# ESP32-S_V2.net
KiCad netlist of a schematic drawn in EasyEDA Pro
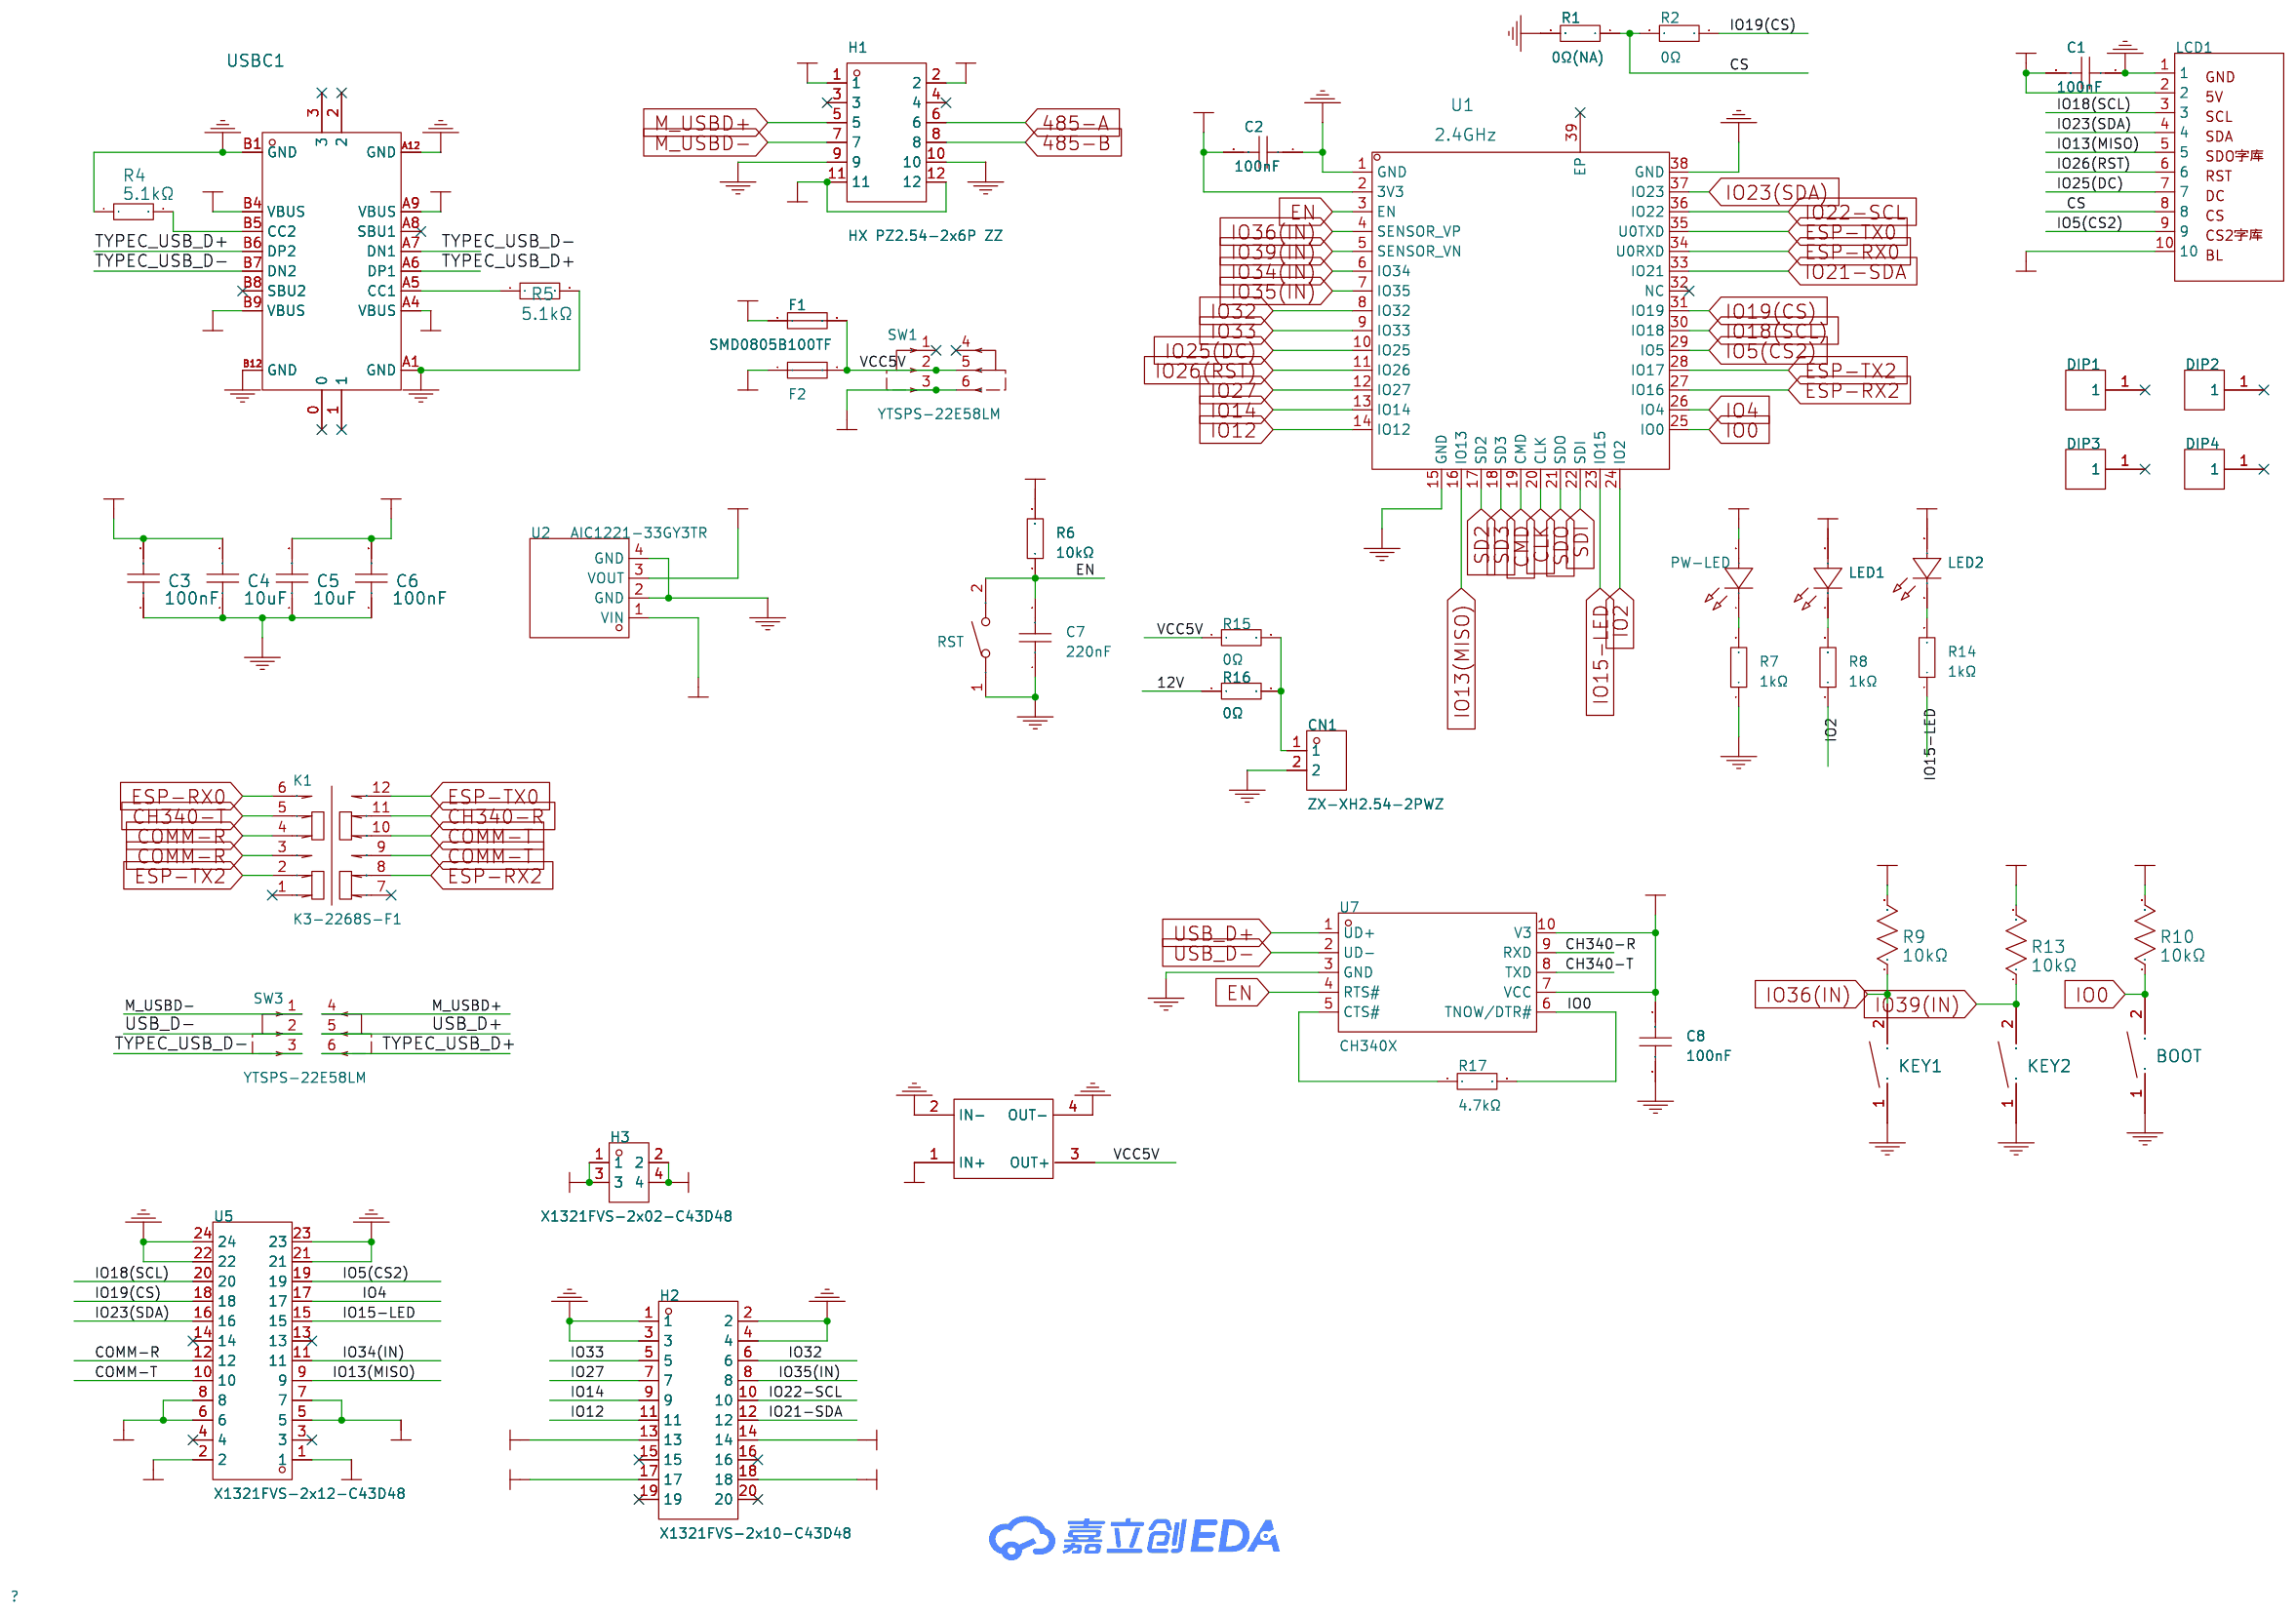
[diagram p0: schematic sheet]

(export (version "E")
  (design (tool "Eeschema 10.0.6"))
  (components
    (comp (ref "BOOT")
      (value "TS-1088-AR02016")
      (fields (field (name "Manufacturer") "XUNPU(讯普)"))
      (libsource (lib "easyedapro") (part "TSA343G00D-250J2"))
    )
    (comp (ref "C1")
      (value "100nF")
      (footprint "easyedapro:C0603")
      (description "容值:100nF;精度:±10%;额定电压:50V;材质(温度系数):X7R;")
      (fields
        (field (name "Manufacturer Part") "CC0603KRX7R9BB104")
        (field (name "Manufacturer") "YAGEO(国巨)")
      )
      (libsource (lib "easyedapro") (part "CC0603KRX7R9BB104"))
    )
    (comp (ref "C2")
      (value "100nF")
      (footprint "easyedapro:C0603")
      (description "容值:100nF;精度:±10%;额定电压:50V;材质(温度系数):X7R;")
      (fields
        (field (name "Manufacturer Part") "CC0603KRX7R9BB104")
        (field (name "Manufacturer") "YAGEO(国巨)")
      )
      (libsource (lib "easyedapro") (part "CC0603KRX7R9BB104"))
    )
    (comp (ref "C3")
      (value "100nF")
      (fields
        (field (name "Manufacturer Part") "CC0603KRX7R9BB104")
        (field (name "Manufacturer") "YAGEO(国巨)")
      )
      (libsource (lib "easyedapro") (part "0.1u"))
    )
    (comp (ref "C4")
      (value "10uF")
      (fields
        (field (name "Manufacturer Part") "CL21A106KAYNNNE")
        (field (name "Manufacturer") "SAMSUNG(三星)")
      )
      (libsource (lib "easyedapro") (part "10u"))
    )
    (comp (ref "C5")
      (value "10uF")
      (fields
        (field (name "Manufacturer Part") "CL21A106KAYNNNE")
        (field (name "Manufacturer") "SAMSUNG(三星)")
      )
      (libsource (lib "easyedapro") (part "10u"))
    )
    (comp (ref "C6")
      (value "100nF")
      (fields
        (field (name "Manufacturer Part") "CC0603KRX7R9BB104")
        (field (name "Manufacturer") "YAGEO(国巨)")
      )
      (libsource (lib "easyedapro") (part "0.1u"))
    )
    (comp (ref "C7")
      (value "220nF")
      (footprint "easyedapro:C0603")
      (description "容值:100nF;精度:±10%;额定电压:50V;材质(温度系数):X7R;")
      (fields
        (field (name "Manufacturer Part") "CC0603KRX7R9BB104")
        (field (name "Manufacturer") "YAGEO(国巨)")
      )
      (libsource (lib "easyedapro") (part "CC0603KRX7R9BB104"))
    )
    (comp (ref "C8")
      (value "100nF")
      (footprint "easyedapro:C0603")
      (description "容值:100nF;精度:±10%;额定电压:50V;材质(温度系数):X7R;")
      (fields
        (field (name "Manufacturer Part") "CC0603KRX7R9BB104")
        (field (name "Manufacturer") "YAGEO(国巨)")
      )
      (libsource (lib "easyedapro") (part "CC0603KRX7R9BB104"))
    )
    (comp (ref "CN1")
      (value "ZX-XH2.54-2PWZ")
      (footprint "easyedapro:CONN-TH_2P-P2.50_ZX-XH2.54-2PWZ")
      (fields (field (name "Manufacturer") "Megastar(兆星)"))
      (libsource (lib "easyedapro") (part "ZX-XH2.54-2PWZ"))
    )
    (comp (ref "DIP1")
      (value "~")
      (footprint "easyedapro:贴片铜柱M3*6+1")
      (libsource (lib "easyedapro") (part "贴片铜柱M3*6+1"))
    )
    (comp (ref "DIP2")
      (value "~")
      (footprint "easyedapro:贴片铜柱M3*6+1")
      (libsource (lib "easyedapro") (part "贴片铜柱M3*6+1"))
    )
    (comp (ref "DIP3")
      (value "~")
      (footprint "easyedapro:贴片铜柱M3*6+1")
      (libsource (lib "easyedapro") (part "贴片铜柱M3*6+1"))
    )
    (comp (ref "DIP4")
      (value "~")
      (footprint "easyedapro:贴片铜柱M3*6+1")
      (libsource (lib "easyedapro") (part "贴片铜柱M3*6+1"))
    )
    (comp (ref "F1")
      (value "SMD0805B100TF")
      (footprint "easyedapro:F0805")
      (description "最大电压:6V;最大电流:100A;保持电流:500mA;跳闸电流:1A;最大动作时间:100ms;")
      (fields (field (name "Manufacturer") "Brightking(台湾君耀)"))
      (libsource (lib "easyedapro") (part "SMD0805B050TF"))
    )
    (comp (ref "F2")
      (value "SMD0805B100TF")
      (footprint "easyedapro:F0805")
      (description "最大电压:6V;最大电流:100A;保持电流:500mA;跳闸电流:1A;最大动作时间:100ms;")
      (fields (field (name "Manufacturer") "Brightking(台湾君耀)"))
      (libsource (lib "easyedapro") (part "SMD0805B050TF"))
    )
    (comp (ref "H1")
      (value "HX PZ2.54-2x6P ZZ")
      (fields (field (name "Manufacturer") "hanxia(韩下)"))
      (libsource (lib "easyedapro") (part "PZ2.54-2X6-11.2"))
    )
    (comp (ref "H2")
      (value "X1321FVS-2x10-C43D48")
      (footprint "easyedapro:HDR-SMD_20P-P1.27-V-F-R2-C10-LS4.8")
      (fields (field (name "Manufacturer") "XKB Connectivity(中国星坤)"))
      (libsource (lib "easyedapro") (part "X1321FVS-2X10-C43D48"))
    )
    (comp (ref "H3")
      (value "X1321FVS-2x02-C43D48")
      (footprint "easyedapro:HDR-SMD_4P-P1.27-V-F-R2-C2-LS4.8")
      (fields (field (name "Manufacturer") "XKB Connectivity(中国星坤)"))
      (libsource (lib "easyedapro") (part "X1321FVS-2X02-C43D48"))
    )
    (comp (ref "K1")
      (value "5.1kΩ")
      (footprint "easyedapro:SW-TH_K3-2268S-F1")
      (description "额定电流(DC):300mA;额定电压(DC):6V;额定电流(AC):-;额定电压(AC):-;电路结构:四刀双掷;安装方式:卧贴;机械寿命:1万次;开关颜色:黑色;")
      (fields (field (name "Manufacturer Part") "K3-2268S-F1") (field (name "Manufacturer") "韩国韩荣"))
      (libsource (lib "easyedapro") (part "K3-2268S-F1"))
    )
    (comp (ref "KEY1")
      (value "TS665WS")
      (fields (field (name "Manufacturer") "SHOU HAN(首韩)"))
      (libsource (lib "easyedapro") (part "TSA343G00D-250J2"))
    )
    (comp (ref "KEY2")
      (value "TS665WS")
      (fields (field (name "Manufacturer") "SHOU HAN(首韩)"))
      (libsource (lib "easyedapro") (part "TSA343G00D-250J2"))
    )
    (comp (ref "LCD1")
      (value "~")
      (footprint "easyedapro:1.54寸带字库液晶屏")
      (libsource (lib "easyedapro") (part "1.54寸带字库液晶屏"))
    )
    (comp (ref "LED1")
      (value "XL-1608UBC-04")
      (footprint "easyedapro:LED0603-RD_BLUE")
      (fields (field (name "Manufacturer") "XINGLIGHT(成兴光)"))
      (libsource (lib "easyedapro") (part "XL-1608UBC-04"))
    )
    (comp (ref "LED2")
      (value "XL-1608UBC-04")
      (footprint "easyedapro:LED0603-RD_BLUE")
      (fields (field (name "Manufacturer") "XINGLIGHT(成兴光)"))
      (libsource (lib "easyedapro") (part "XL-1608UBC-04"))
    )
    (comp (ref "PW-LED")
      (value "XL-1608UBC-04")
      (footprint "easyedapro:LED0603-RD_BLUE")
      (fields (field (name "Manufacturer") "XINGLIGHT(成兴光)"))
      (libsource (lib "easyedapro") (part "XL-1608UBC-04"))
    )
    (comp (ref "R1")
      (value "0Ω(NA)")
      (footprint "easyedapro:R0603")
      (description "电阻类型:厚膜电阻;阻值:0Ω;精度:±1%;功率:100mW;最大工作电压:75V;")
      (fields
        (field (name "Manufacturer Part") "0603WAF0000T5E")
        (field (name "Manufacturer") "UNI-ROYAL(厚声)")
      )
      (libsource (lib "easyedapro") (part "0603WAF0000T5E"))
    )
    (comp (ref "R2")
      (value "0Ω")
      (footprint "easyedapro:R0603")
      (description "电阻类型:厚膜电阻;阻值:0Ω;精度:±1%;功率:100mW;最大工作电压:75V;")
      (fields
        (field (name "Manufacturer Part") "0603WAF0000T5E")
        (field (name "Manufacturer") "UNI-ROYAL(厚声)")
      )
      (libsource (lib "easyedapro") (part "0603WAF0000T5E"))
    )
    (comp (ref "R4") (value "5.1kΩ") (libsource (lib "easyedapro") (part "5.1K")))
    (comp (ref "R5") (value "5.1kΩ") (libsource (lib "easyedapro") (part "5.1K")))
    (comp (ref "R6")
      (value "10kΩ")
      (footprint "easyedapro:R0603")
      (description "电阻类型:厚膜电阻;阻值:10kΩ;精度:±1%;功率:100mW;最大工作电压:75V;温度系数:±100ppm/°C;")
      (fields
        (field (name "Manufacturer Part") "0603WAF1002T5E")
        (field (name "Manufacturer") "UNI-ROYAL(厚声)")
      )
      (libsource (lib "easyedapro") (part "0603WAF1002T5E"))
    )
    (comp (ref "R7")
      (value "1kΩ")
      (footprint "easyedapro:R0603")
      (description "电阻类型:厚膜电阻;阻值:1kΩ;精度:±1%;功率:100mW;最大工作电压:75V;温度系数:±100ppm/°C;")
      (fields
        (field (name "Manufacturer Part") "0603WAF1001T5E")
        (field (name "Manufacturer") "UNI-ROYAL(厚声)")
      )
      (libsource (lib "easyedapro") (part "0603WAF1001T5E"))
    )
    (comp (ref "R8")
      (value "1kΩ")
      (footprint "easyedapro:R0603")
      (description "电阻类型:厚膜电阻;阻值:1kΩ;精度:±1%;功率:100mW;最大工作电压:75V;温度系数:±100ppm/°C;")
      (fields
        (field (name "Manufacturer Part") "0603WAF1001T5E")
        (field (name "Manufacturer") "UNI-ROYAL(厚声)")
      )
      (libsource (lib "easyedapro") (part "0603WAF1001T5E"))
    )
    (comp (ref "R9")
      (value "10kΩ")
      (fields
        (field (name "Manufacturer Part") "0603WAF1002T5E")
        (field (name "Manufacturer") "UNI-ROYAL(厚声)")
      )
      (libsource (lib "easyedapro") (part "10k"))
    )
    (comp (ref "R10")
      (value "10kΩ")
      (fields
        (field (name "Manufacturer Part") "0603WAF1002T5E")
        (field (name "Manufacturer") "UNI-ROYAL(厚声)")
      )
      (libsource (lib "easyedapro") (part "10k"))
    )
    (comp (ref "R13")
      (value "10kΩ")
      (fields
        (field (name "Manufacturer Part") "0603WAF1002T5E")
        (field (name "Manufacturer") "UNI-ROYAL(厚声)")
      )
      (libsource (lib "easyedapro") (part "10k"))
    )
    (comp (ref "R14")
      (value "1kΩ")
      (footprint "easyedapro:R0603")
      (description "电阻类型:厚膜电阻;阻值:1kΩ;精度:±1%;功率:100mW;最大工作电压:75V;温度系数:±100ppm/°C;")
      (fields
        (field (name "Manufacturer Part") "0603WAF1001T5E")
        (field (name "Manufacturer") "UNI-ROYAL(厚声)")
      )
      (libsource (lib "easyedapro") (part "0603WAF1001T5E"))
    )
    (comp (ref "R15")
      (value "0Ω")
      (footprint "easyedapro:R0603")
      (description "电阻类型:厚膜电阻;阻值:0Ω;精度:±1%;功率:100mW;最大工作电压:75V;")
      (fields
        (field (name "Manufacturer Part") "0603WAF0000T5E")
        (field (name "Manufacturer") "UNI-ROYAL(厚声)")
      )
      (libsource (lib "easyedapro") (part "0603WAF0000T5E"))
    )
    (comp (ref "R16")
      (value "0Ω")
      (footprint "easyedapro:R0603")
      (description "电阻类型:厚膜电阻;阻值:0Ω;精度:±1%;功率:100mW;最大工作电压:75V;")
      (fields
        (field (name "Manufacturer Part") "0603WAF0000T5E")
        (field (name "Manufacturer") "UNI-ROYAL(厚声)")
      )
      (libsource (lib "easyedapro") (part "0603WAF0000T5E"))
    )
    (comp (ref "R17")
      (value "4.7kΩ")
      (footprint "easyedapro:R0603")
      (description "电阻类型:厚膜电阻;阻值:4.7kΩ;精度:±1%;功率:100mW;最大工作电压:75V;温度系数:±100ppm/°C;")
      (fields
        (field (name "Manufacturer Part") "0603WAF4701T5E")
        (field (name "Manufacturer") "UNI-ROYAL(厚声)")
      )
      (libsource (lib "easyedapro") (part "0603WAF4701T5E"))
    )
    (comp (ref "RST")
      (value "TS-1088-AR02016")
      (footprint "easyedapro:SW-SMD_L3.9-W3.0-P4.45")
      (fields (field (name "Manufacturer") "XUNPU(讯普)"))
      (libsource (lib "easyedapro") (part "TS-1088-AR02016"))
    )
    (comp (ref "SW1")
      (value "YTSPS-22E58LM")
      (footprint "easyedapro:SW-SMD_6P-L5.8-W5.8-P2.00-LS8.0_YTSPS-22E58LM")
      (description "电路结构:双刀双掷;自锁/无锁:自锁;安装方式:立贴;触点电流:500mA;额定电压 (DC):50V;作用力:1.8N;机械寿命:2万次;")
      (fields (field (name "Manufacturer") "YIYUAN(怡远)"))
      (libsource (lib "easyedapro") (part "YTSPS-22E58LM"))
    )
    (comp (ref "SW3")
      (value "YTSPS-22E58LM")
      (footprint "easyedapro:SW-SMD_6P-L5.8-W5.8-P2.00-LS8.0_YTSPS-22E58LM")
      (description "电路结构:双刀双掷;自锁/无锁:自锁;安装方式:立贴;触点电流:500mA;额定电压 (DC):50V;作用力:1.8N;机械寿命:2万次;")
      (fields (field (name "Manufacturer") "YIYUAN(怡远)"))
      (libsource (lib "easyedapro") (part "YTSPS-22E58LM"))
    )
    (comp (ref "U1")
      (value "2.4GHz")
      (fields (field (name "Manufacturer Part") "ESP32-S") (field (name "Manufacturer") "Ai-Thinker(安信可)"))
      (libsource (lib "easyedapro") (part "ESP32-S"))
    )
    (comp (ref "U2")
      (value "AIC1221-33GY3TR")
      (footprint "easyedapro:SOT-223_L6.5-W3.5-P2.30-LS7.0-BR")
      (description "输出类型:固定;输出极性:正;最大输入电压:6V;输出电压:3.3V;输出电流:2A;电源纹波抑制比(PSRR):70dB@(1kHz);")
      (fields (field (name "Manufacturer") "AIC(沛亨半导体)"))
      (libsource (lib "easyedapro") (part "AIC1221-33GY3TR"))
    )
    (comp (ref "U5")
      (value "X1321FVS-2x12-C43D48")
      (footprint "easyedapro:HDR-SMD_24P-P1.27-V-F-R2-C12-LS4.8")
      (fields (field (name "Manufacturer") "XKB Connectivity(中国星坤)"))
      (libsource (lib "easyedapro") (part "X1321FVS-2X12-C43D48"))
    )
    (comp (ref "U6")
      (value "~")
      (footprint "easyedapro:DC-DCmini")
      (libsource (lib "easyedapro") (part "DC-DC模块mini"))
    )
    (comp (ref "U7")
      (value "CH340X")
      (footprint "easyedapro:MSOP-10_L3.0-W3.0-P0.50-LS5.0-BL")
      (fields (field (name "Manufacturer") "WCH(南京沁恒)"))
      (libsource (lib "easyedapro") (part "CH340X"))
    )
    (comp (ref "USBC1") (value "TYPE-C-31-M-12") (libsource (lib "easyedapro") (part "type-c-31-m-12")))
  )
  (nets
    (net (code "1") (name "/CS") (class "Default")
      (node (ref "LCD1") (pin "8") (pinfunction "8_8") (pintype "unspecified"))
      (node (ref "R1") (pin "1") (pinfunction "1_1") (pintype "input"))
      (node (ref "R2") (pin "2") (pinfunction "2_2") (pintype "input"))
    )
    (net (code "2") (name "/TYPEC_USB_D+") (class "Default")
      (node (ref "SW3") (pin "6") (pinfunction "6_6") (pintype "unspecified"))
      (node (ref "USBC1") (pin "A6") (pinfunction "DP1_A6") (pintype "input"))
      (node (ref "USBC1") (pin "B6") (pinfunction "DP2_B6") (pintype "input"))
    )
    (net (code "3") (name "/TYPEC_USB_D-") (class "Default")
      (node (ref "SW3") (pin "3") (pinfunction "3_3") (pintype "unspecified"))
      (node (ref "USBC1") (pin "A7") (pinfunction "DN1_A7") (pintype "input"))
      (node (ref "USBC1") (pin "B7") (pinfunction "DN2_B7") (pintype "input"))
    )
    (net (code "4") (name "/VCC5V") (class "Default")
      (node (ref "F1") (pin "2") (pinfunction "2_2") (pintype "input"))
      (node (ref "F2") (pin "2") (pinfunction "2_2") (pintype "input"))
      (node (ref "R15") (pin "1") (pinfunction "1_1") (pintype "input"))
      (node (ref "SW1") (pin "2") (pinfunction "2_2") (pintype "unspecified"))
      (node (ref "SW1") (pin "5") (pinfunction "5_5") (pintype "unspecified"))
      (node (ref "U6") (pin "3") (pinfunction "OUT+_3") (pintype "input"))
    )
    (net (code "5") (name "3.3V") (class "Default")
      (node (ref "C2") (pin "2") (pinfunction "2_2") (pintype "unspecified"))
      (node (ref "C5") (pin "2") (pinfunction "2_2") (pintype "input"))
      (node (ref "C6") (pin "2") (pinfunction "2_2") (pintype "input"))
      (node (ref "C8") (pin "1") (pinfunction "1_1") (pintype "unspecified"))
      (node (ref "H2") (pin "13") (pinfunction "13_13") (pintype "unspecified"))
      (node (ref "H2") (pin "14") (pinfunction "14_14") (pintype "unspecified"))
      (node (ref "LCD1") (pin "10") (pinfunction "10_10") (pintype "unspecified"))
      (node (ref "LED1") (pin "2") (pinfunction "A_2") (pintype "unspecified"))
      (node (ref "LED2") (pin "2") (pinfunction "A_2") (pintype "unspecified"))
      (node (ref "PW-LED") (pin "2") (pinfunction "A_2") (pintype "unspecified"))
      (node (ref "R10") (pin "2") (pinfunction "2_2") (pintype "input"))
      (node (ref "R13") (pin "2") (pinfunction "2_2") (pintype "input"))
      (node (ref "R6") (pin "2") (pinfunction "2_2") (pintype "input"))
      (node (ref "R9") (pin "2") (pinfunction "2_2") (pintype "input"))
      (node (ref "U1") (pin "2") (pinfunction "3V3_2") (pintype "input"))
      (node (ref "U2") (pin "3") (pinfunction "VOUT_3") (pintype "input"))
      (node (ref "U5") (pin "5") (pinfunction "5_5") (pintype "unspecified"))
      (node (ref "U5") (pin "6") (pinfunction "6_6") (pintype "unspecified"))
      (node (ref "U5") (pin "7") (pinfunction "7_7") (pintype "unspecified"))
      (node (ref "U5") (pin "8") (pinfunction "8_8") (pintype "unspecified"))
      (node (ref "U7") (pin "10") (pinfunction "V3_10") (pintype "unspecified"))
      (node (ref "U7") (pin "7") (pinfunction "VCC_7") (pintype "unspecified"))
    )
    (net (code "6") (name "5V") (class "Default")
      (node (ref "C1") (pin "2") (pinfunction "2_2") (pintype "unspecified"))
      (node (ref "C3") (pin "2") (pinfunction "2_2") (pintype "input"))
      (node (ref "C4") (pin "2") (pinfunction "2_2") (pintype "input"))
      (node (ref "H2") (pin "17") (pinfunction "17_17") (pintype "unspecified"))
      (node (ref "H2") (pin "18") (pinfunction "18_18") (pintype "unspecified"))
      (node (ref "LCD1") (pin "2") (pinfunction "2_2") (pintype "unspecified"))
      (node (ref "SW1") (pin "3") (pinfunction "3_3") (pintype "unspecified"))
      (node (ref "SW1") (pin "6") (pinfunction "6_6") (pintype "unspecified"))
      (node (ref "U2") (pin "1") (pinfunction "VIN_1") (pintype "input"))
      (node (ref "U5") (pin "1") (pinfunction "1_1") (pintype "unspecified"))
      (node (ref "U5") (pin "2") (pinfunction "2_2") (pintype "unspecified"))
    )
    (net (code "7") (name "12V") (class "Default")
      (node (ref "H1") (pin "1") (pinfunction "1_1") (pintype "unspecified"))
      (node (ref "H1") (pin "2") (pinfunction "2_2") (pintype "unspecified"))
      (node (ref "H3") (pin "1") (pinfunction "1_1") (pintype "unspecified"))
      (node (ref "H3") (pin "2") (pinfunction "2_2") (pintype "unspecified"))
      (node (ref "H3") (pin "3") (pinfunction "3_3") (pintype "unspecified"))
      (node (ref "H3") (pin "4") (pinfunction "4_4") (pintype "unspecified"))
      (node (ref "R16") (pin "1") (pinfunction "1_1") (pintype "input"))
      (node (ref "U6") (pin "1") (pinfunction "IN+_1") (pintype "input"))
    )
    (net (code "8") (name "485-A") (class "Default")
      (node (ref "H1") (pin "6") (pinfunction "6_6") (pintype "unspecified"))
    )
    (net (code "9") (name "485-B") (class "Default")
      (node (ref "H1") (pin "8") (pinfunction "8_8") (pintype "unspecified"))
    )
    (net (code "10") (name "CH340-R") (class "Default")
      (node (ref "K1") (pin "11") (pinfunction "11_11") (pintype "input"))
      (node (ref "U7") (pin "9") (pinfunction "RXD_9") (pintype "unspecified"))
    )
    (net (code "11") (name "CH340-T") (class "Default")
      (node (ref "K1") (pin "5") (pinfunction "5_5") (pintype "input"))
      (node (ref "U7") (pin "8") (pinfunction "TXD_8") (pintype "unspecified"))
    )
    (net (code "12") (name "CLK") (class "Default")
      (node (ref "U1") (pin "20") (pinfunction "CLK_20") (pintype "input"))
    )
    (net (code "13") (name "CMD") (class "Default")
      (node (ref "U1") (pin "19") (pinfunction "CMD_19") (pintype "input"))
    )
    (net (code "14") (name "COMM-R") (class "Default")
      (node (ref "K1") (pin "3") (pinfunction "3_3") (pintype "input"))
      (node (ref "K1") (pin "4") (pinfunction "4_4") (pintype "input"))
      (node (ref "U5") (pin "12") (pinfunction "12_12") (pintype "unspecified"))
    )
    (net (code "15") (name "COMM-T") (class "Default")
      (node (ref "K1") (pin "10") (pinfunction "10_10") (pintype "input"))
      (node (ref "K1") (pin "9") (pinfunction "9_9") (pintype "input"))
      (node (ref "U5") (pin "10") (pinfunction "10_10") (pintype "unspecified"))
    )
    (net (code "16") (name "EN") (class "Default")
      (node (ref "C7") (pin "2") (pinfunction "2_2") (pintype "unspecified"))
      (node (ref "R6") (pin "1") (pinfunction "1_1") (pintype "input"))
      (node (ref "RST") (pin "2") (pinfunction "2_2") (pintype "unspecified"))
      (node (ref "U1") (pin "3") (pinfunction "EN_3") (pintype "input"))
      (node (ref "U7") (pin "4") (pinfunction "RTS#_4") (pintype "unspecified"))
    )
    (net (code "17") (name "ESP-RX0") (class "Default")
      (node (ref "K1") (pin "6") (pinfunction "6_6") (pintype "input"))
      (node (ref "U1") (pin "34") (pinfunction "U0RXD_34") (pintype "input"))
    )
    (net (code "18") (name "ESP-RX2") (class "Default")
      (node (ref "K1") (pin "8") (pinfunction "8_8") (pintype "input"))
      (node (ref "U1") (pin "27") (pinfunction "IO16_27") (pintype "input"))
    )
    (net (code "19") (name "ESP-TX0") (class "Default")
      (node (ref "K1") (pin "12") (pinfunction "12_12") (pintype "input"))
      (node (ref "U1") (pin "35") (pinfunction "U0TXD_35") (pintype "input"))
    )
    (net (code "20") (name "ESP-TX2") (class "Default")
      (node (ref "K1") (pin "2") (pinfunction "2_2") (pintype "input"))
      (node (ref "U1") (pin "28") (pinfunction "IO17_28") (pintype "input"))
    )
    (net (code "21") (name "GND") (class "Default")
      (node (ref "BOOT") (pin "1") (pinfunction "1_1") (pintype "input"))
      (node (ref "C1") (pin "1") (pinfunction "1_1") (pintype "unspecified"))
      (node (ref "C2") (pin "1") (pinfunction "1_1") (pintype "unspecified"))
      (node (ref "C3") (pin "1") (pinfunction "1_1") (pintype "input"))
      (node (ref "C4") (pin "1") (pinfunction "1_1") (pintype "input"))
      (node (ref "C5") (pin "1") (pinfunction "1_1") (pintype "input"))
      (node (ref "C6") (pin "1") (pinfunction "1_1") (pintype "input"))
      (node (ref "C7") (pin "1") (pinfunction "1_1") (pintype "unspecified"))
      (node (ref "C8") (pin "2") (pinfunction "2_2") (pintype "unspecified"))
      (node (ref "CN1") (pin "2") (pinfunction "2_2") (pintype "unspecified"))
      (node (ref "H1") (pin "10") (pinfunction "10_10") (pintype "unspecified"))
      (node (ref "H1") (pin "9") (pinfunction "9_9") (pintype "unspecified"))
      (node (ref "H2") (pin "1") (pinfunction "1_1") (pintype "unspecified"))
      (node (ref "H2") (pin "2") (pinfunction "2_2") (pintype "unspecified"))
      (node (ref "H2") (pin "3") (pinfunction "3_3") (pintype "unspecified"))
      (node (ref "H2") (pin "4") (pinfunction "4_4") (pintype "unspecified"))
      (node (ref "KEY1") (pin "1") (pinfunction "1_1") (pintype "input"))
      (node (ref "KEY2") (pin "1") (pinfunction "1_1") (pintype "input"))
      (node (ref "LCD1") (pin "1") (pinfunction "1_1") (pintype "unspecified"))
      (node (ref "R1") (pin "2") (pinfunction "2_2") (pintype "input"))
      (node (ref "R4") (pin "1") (pinfunction "1_1") (pintype "input"))
      (node (ref "R5") (pin "2") (pinfunction "2_2") (pintype "input"))
      (node (ref "R7") (pin "1") (pinfunction "1_1") (pintype "input"))
      (node (ref "RST") (pin "1") (pinfunction "1_1") (pintype "unspecified"))
      (node (ref "U1") (pin "1") (pinfunction "GND_1") (pintype "input"))
      (node (ref "U1") (pin "15") (pinfunction "GND_15") (pintype "input"))
      (node (ref "U1") (pin "38") (pinfunction "GND_38") (pintype "input"))
      (node (ref "U2") (pin "2") (pinfunction "GND_2") (pintype "input"))
      (node (ref "U2") (pin "4") (pinfunction "GND_4") (pintype "input"))
      (node (ref "U5") (pin "21") (pinfunction "21_21") (pintype "unspecified"))
      (node (ref "U5") (pin "22") (pinfunction "22_22") (pintype "unspecified"))
      (node (ref "U5") (pin "23") (pinfunction "23_23") (pintype "unspecified"))
      (node (ref "U5") (pin "24") (pinfunction "24_24") (pintype "unspecified"))
      (node (ref "U6") (pin "2") (pinfunction "IN-_2") (pintype "input"))
      (node (ref "U6") (pin "4") (pinfunction "OUT-_4") (pintype "input"))
      (node (ref "U7") (pin "3") (pinfunction "GND_3") (pintype "unspecified"))
      (node (ref "USBC1") (pin "A1") (pinfunction "GND_A1") (pintype "input"))
      (node (ref "USBC1") (pin "A12") (pinfunction "GND_A12") (pintype "input"))
      (node (ref "USBC1") (pin "B1") (pinfunction "GND_B1") (pintype "input"))
      (node (ref "USBC1") (pin "B12") (pinfunction "GND_B12") (pintype "input"))
    )
    (net (code "22") (name "IO0") (class "Default")
      (node (ref "BOOT") (pin "2") (pinfunction "2_2") (pintype "input"))
      (node (ref "R10") (pin "1") (pinfunction "1_1") (pintype "input"))
      (node (ref "R17") (pin "2") (pinfunction "2_2") (pintype "input"))
      (node (ref "U1") (pin "25") (pinfunction "IO0_25") (pintype "input"))
      (node (ref "U7") (pin "6") (pinfunction "TNOW/DTR#_6") (pintype "unspecified"))
    )
    (net (code "23") (name "IO2") (class "Default")
      (node (ref "R8") (pin "1") (pinfunction "1_1") (pintype "input"))
      (node (ref "U1") (pin "24") (pinfunction "IO2_24") (pintype "input"))
    )
    (net (code "24") (name "IO4") (class "Default")
      (node (ref "U1") (pin "26") (pinfunction "IO4_26") (pintype "input"))
      (node (ref "U5") (pin "17") (pinfunction "17_17") (pintype "unspecified"))
    )
    (net (code "25") (name "IO5(CS2)") (class "Default")
      (node (ref "LCD1") (pin "9") (pinfunction "9_9") (pintype "unspecified"))
      (node (ref "U1") (pin "29") (pinfunction "IO5_29") (pintype "input"))
      (node (ref "U5") (pin "19") (pinfunction "19_19") (pintype "unspecified"))
    )
    (net (code "26") (name "IO12") (class "Default")
      (node (ref "H2") (pin "11") (pinfunction "11_11") (pintype "unspecified"))
      (node (ref "U1") (pin "14") (pinfunction "IO12_14") (pintype "input"))
    )
    (net (code "27") (name "IO13(MISO)") (class "Default")
      (node (ref "LCD1") (pin "5") (pinfunction "5_5") (pintype "unspecified"))
      (node (ref "U1") (pin "16") (pinfunction "IO13_16") (pintype "input"))
      (node (ref "U5") (pin "9") (pinfunction "9_9") (pintype "unspecified"))
    )
    (net (code "28") (name "IO14") (class "Default")
      (node (ref "H2") (pin "9") (pinfunction "9_9") (pintype "unspecified"))
      (node (ref "U1") (pin "13") (pinfunction "IO14_13") (pintype "input"))
    )
    (net (code "29") (name "IO15-LED") (class "Default")
      (node (ref "R14") (pin "1") (pinfunction "1_1") (pintype "input"))
      (node (ref "U1") (pin "23") (pinfunction "IO15_23") (pintype "input"))
      (node (ref "U5") (pin "15") (pinfunction "15_15") (pintype "unspecified"))
    )
    (net (code "30") (name "IO18(SCL)") (class "Default")
      (node (ref "LCD1") (pin "3") (pinfunction "3_3") (pintype "unspecified"))
      (node (ref "U1") (pin "30") (pinfunction "IO18_30") (pintype "input"))
      (node (ref "U5") (pin "20") (pinfunction "20_20") (pintype "unspecified"))
    )
    (net (code "31") (name "IO19(CS)") (class "Default")
      (node (ref "R2") (pin "1") (pinfunction "1_1") (pintype "input"))
      (node (ref "U1") (pin "31") (pinfunction "IO19_31") (pintype "input"))
      (node (ref "U5") (pin "18") (pinfunction "18_18") (pintype "unspecified"))
    )
    (net (code "32") (name "IO21-SDA") (class "Default")
      (node (ref "H2") (pin "12") (pinfunction "12_12") (pintype "unspecified"))
      (node (ref "U1") (pin "33") (pinfunction "IO21_33") (pintype "input"))
    )
    (net (code "33") (name "IO22-SCL") (class "Default")
      (node (ref "H2") (pin "10") (pinfunction "10_10") (pintype "unspecified"))
      (node (ref "U1") (pin "36") (pinfunction "IO22_36") (pintype "input"))
    )
    (net (code "34") (name "IO23(SDA)") (class "Default")
      (node (ref "LCD1") (pin "4") (pinfunction "4_4") (pintype "unspecified"))
      (node (ref "U1") (pin "37") (pinfunction "IO23_37") (pintype "input"))
      (node (ref "U5") (pin "16") (pinfunction "16_16") (pintype "unspecified"))
    )
    (net (code "35") (name "IO25(DC)") (class "Default")
      (node (ref "LCD1") (pin "7") (pinfunction "7_7") (pintype "unspecified"))
      (node (ref "U1") (pin "10") (pinfunction "IO25_10") (pintype "input"))
    )
    (net (code "36") (name "IO26(RST)") (class "Default")
      (node (ref "LCD1") (pin "6") (pinfunction "6_6") (pintype "unspecified"))
      (node (ref "U1") (pin "11") (pinfunction "IO26_11") (pintype "input"))
    )
    (net (code "37") (name "IO27") (class "Default")
      (node (ref "H2") (pin "7") (pinfunction "7_7") (pintype "unspecified"))
      (node (ref "U1") (pin "12") (pinfunction "IO27_12") (pintype "input"))
    )
    (net (code "38") (name "IO32") (class "Default")
      (node (ref "H2") (pin "6") (pinfunction "6_6") (pintype "unspecified"))
      (node (ref "U1") (pin "8") (pinfunction "IO32_8") (pintype "input"))
    )
    (net (code "39") (name "IO33") (class "Default")
      (node (ref "H2") (pin "5") (pinfunction "5_5") (pintype "unspecified"))
      (node (ref "U1") (pin "9") (pinfunction "IO33_9") (pintype "input"))
    )
    (net (code "40") (name "IO34(IN)") (class "Default")
      (node (ref "U1") (pin "6") (pinfunction "IO34_6") (pintype "input"))
      (node (ref "U5") (pin "11") (pinfunction "11_11") (pintype "unspecified"))
    )
    (net (code "41") (name "IO35(IN)") (class "Default")
      (node (ref "H2") (pin "8") (pinfunction "8_8") (pintype "unspecified"))
      (node (ref "U1") (pin "7") (pinfunction "IO35_7") (pintype "input"))
    )
    (net (code "42") (name "IO36(IN)") (class "Default")
      (node (ref "KEY1") (pin "2") (pinfunction "2_2") (pintype "input"))
      (node (ref "R9") (pin "1") (pinfunction "1_1") (pintype "input"))
      (node (ref "U1") (pin "4") (pinfunction "SENSOR_VP_4") (pintype "input"))
    )
    (net (code "43") (name "IO39(IN)") (class "Default")
      (node (ref "KEY2") (pin "2") (pinfunction "2_2") (pintype "input"))
      (node (ref "R13") (pin "1") (pinfunction "1_1") (pintype "input"))
      (node (ref "U1") (pin "5") (pinfunction "SENSOR_VN_5") (pintype "input"))
    )
    (net (code "44") (name "M_USBD+") (class "Default")
      (node (ref "H1") (pin "5") (pinfunction "5_5") (pintype "unspecified"))
      (node (ref "SW3") (pin "4") (pinfunction "4_4") (pintype "unspecified"))
    )
    (net (code "45") (name "M_USBD-") (class "Default")
      (node (ref "H1") (pin "7") (pinfunction "7_7") (pintype "unspecified"))
      (node (ref "SW3") (pin "1") (pinfunction "1_1") (pintype "unspecified"))
    )
    (net (code "46") (name "M_VCC") (class "Default")
      (node (ref "F2") (pin "1") (pinfunction "1_1") (pintype "input"))
      (node (ref "H1") (pin "11") (pinfunction "11_11") (pintype "unspecified"))
      (node (ref "H1") (pin "12") (pinfunction "12_12") (pintype "unspecified"))
    )
    (net (code "47") (name "Net-(CN1-Pad1)") (class "Default")
      (node (ref "CN1") (pin "1") (pinfunction "1_1") (pintype "unspecified"))
      (node (ref "R15") (pin "2") (pinfunction "2_2") (pintype "input"))
      (node (ref "R16") (pin "2") (pinfunction "2_2") (pintype "input"))
    )
    (net (code "48") (name "Net-(LED1-K)") (class "Default")
      (node (ref "LED1") (pin "1") (pinfunction "K_1") (pintype "unspecified"))
      (node (ref "R8") (pin "2") (pinfunction "2_2") (pintype "input"))
    )
    (net (code "49") (name "Net-(LED2-K)") (class "Default")
      (node (ref "LED2") (pin "1") (pinfunction "K_1") (pintype "unspecified"))
      (node (ref "R14") (pin "2") (pinfunction "2_2") (pintype "input"))
    )
    (net (code "50") (name "Net-(PW-LED-K)") (class "Default")
      (node (ref "PW-LED") (pin "1") (pinfunction "K_1") (pintype "unspecified"))
      (node (ref "R7") (pin "2") (pinfunction "2_2") (pintype "input"))
    )
    (net (code "51") (name "Net-(U7-CTS#)") (class "Default")
      (node (ref "R17") (pin "1") (pinfunction "1_1") (pintype "input"))
      (node (ref "U7") (pin "5") (pinfunction "CTS#_5") (pintype "unspecified"))
    )
    (net (code "52") (name "Net-(USBC1-CC1)") (class "Default")
      (node (ref "R5") (pin "1") (pinfunction "1_1") (pintype "input"))
      (node (ref "USBC1") (pin "A5") (pinfunction "CC1_A5") (pintype "input"))
    )
    (net (code "53") (name "Net-(USBC1-CC2)") (class "Default")
      (node (ref "R4") (pin "2") (pinfunction "2_2") (pintype "input"))
      (node (ref "USBC1") (pin "B5") (pinfunction "CC2_B5") (pintype "input"))
    )
    (net (code "54") (name "SD2") (class "Default")
      (node (ref "U1") (pin "17") (pinfunction "SD2_17") (pintype "input"))
    )
    (net (code "55") (name "SD3") (class "Default")
      (node (ref "U1") (pin "18") (pinfunction "SD3_18") (pintype "input"))
    )
    (net (code "56") (name "SDI") (class "Default")
      (node (ref "U1") (pin "22") (pinfunction "SDI_22") (pintype "input"))
    )
    (net (code "57") (name "SDO") (class "Default")
      (node (ref "U1") (pin "21") (pinfunction "SDO_21") (pintype "input"))
    )
    (net (code "58") (name "USB_D+") (class "Default")
      (node (ref "SW3") (pin "5") (pinfunction "5_5") (pintype "unspecified"))
      (node (ref "U7") (pin "1") (pinfunction "UD+_1") (pintype "unspecified"))
    )
    (net (code "59") (name "USB_D-") (class "Default")
      (node (ref "SW3") (pin "2") (pinfunction "2_2") (pintype "unspecified"))
      (node (ref "U7") (pin "2") (pinfunction "UD-_2") (pintype "unspecified"))
    )
    (net (code "60") (name "VBUS") (class "Default")
      (node (ref "F1") (pin "1") (pinfunction "1_1") (pintype "input"))
      (node (ref "USBC1") (pin "A4") (pinfunction "VBUS_A4") (pintype "input"))
      (node (ref "USBC1") (pin "A9") (pinfunction "VBUS_A9") (pintype "input"))
      (node (ref "USBC1") (pin "B4") (pinfunction "VBUS_B4") (pintype "input"))
      (node (ref "USBC1") (pin "B9") (pinfunction "VBUS_B9") (pintype "input"))
    )
    (net (code "61") (name "unconnected-(DIP1-Pad1)") (class "Default")
      (node (ref "DIP1") (pin "1") (pinfunction "1_1") (pintype "input+no_connect"))
    )
    (net (code "62") (name "unconnected-(DIP2-Pad1)") (class "Default")
      (node (ref "DIP2") (pin "1") (pinfunction "1_1") (pintype "input+no_connect"))
    )
    (net (code "63") (name "unconnected-(DIP3-Pad1)") (class "Default")
      (node (ref "DIP3") (pin "1") (pinfunction "1_1") (pintype "input+no_connect"))
    )
    (net (code "64") (name "unconnected-(DIP4-Pad1)") (class "Default")
      (node (ref "DIP4") (pin "1") (pinfunction "1_1") (pintype "input+no_connect"))
    )
    (net (code "65") (name "unconnected-(H1-Pad3)") (class "Default")
      (node (ref "H1") (pin "3") (pinfunction "3_3") (pintype "unspecified+no_connect"))
    )
    (net (code "66") (name "unconnected-(H1-Pad4)") (class "Default")
      (node (ref "H1") (pin "4") (pinfunction "4_4") (pintype "unspecified+no_connect"))
    )
    (net (code "67") (name "unconnected-(H2-Pad15)") (class "Default")
      (node (ref "H2") (pin "15") (pinfunction "15_15") (pintype "unspecified+no_connect"))
    )
    (net (code "68") (name "unconnected-(H2-Pad16)") (class "Default")
      (node (ref "H2") (pin "16") (pinfunction "16_16") (pintype "unspecified+no_connect"))
    )
    (net (code "69") (name "unconnected-(H2-Pad19)") (class "Default")
      (node (ref "H2") (pin "19") (pinfunction "19_19") (pintype "unspecified+no_connect"))
    )
    (net (code "70") (name "unconnected-(H2-Pad20)") (class "Default")
      (node (ref "H2") (pin "20") (pinfunction "20_20") (pintype "unspecified+no_connect"))
    )
    (net (code "71") (name "unconnected-(K1-Pad1)") (class "Default")
      (node (ref "K1") (pin "1") (pinfunction "1_1") (pintype "input+no_connect"))
    )
    (net (code "72") (name "unconnected-(K1-Pad7)") (class "Default")
      (node (ref "K1") (pin "7") (pinfunction "7_7") (pintype "input+no_connect"))
    )
    (net (code "73") (name "unconnected-(SW1-Pad1)") (class "Default")
      (node (ref "SW1") (pin "1") (pinfunction "1_1") (pintype "unspecified+no_connect"))
    )
    (net (code "74") (name "unconnected-(SW1-Pad4)") (class "Default")
      (node (ref "SW1") (pin "4") (pinfunction "4_4") (pintype "unspecified+no_connect"))
    )
    (net (code "75") (name "unconnected-(U1-EP-Pad39)") (class "Default")
      (node (ref "U1") (pin "39") (pinfunction "EP_39") (pintype "input+no_connect"))
    )
    (net (code "76") (name "unconnected-(U1-NC-Pad32)") (class "Default")
      (node (ref "U1") (pin "32") (pinfunction "NC_32") (pintype "input+no_connect"))
    )
    (net (code "77") (name "unconnected-(U5-Pad3)") (class "Default")
      (node (ref "U5") (pin "3") (pinfunction "3_3") (pintype "unspecified+no_connect"))
    )
    (net (code "78") (name "unconnected-(U5-Pad4)") (class "Default")
      (node (ref "U5") (pin "4") (pinfunction "4_4") (pintype "unspecified+no_connect"))
    )
    (net (code "79") (name "unconnected-(U5-Pad13)") (class "Default")
      (node (ref "U5") (pin "13") (pinfunction "13_13") (pintype "unspecified+no_connect"))
    )
    (net (code "80") (name "unconnected-(U5-Pad14)") (class "Default")
      (node (ref "U5") (pin "14") (pinfunction "14_14") (pintype "unspecified+no_connect"))
    )
    (net (code "81") (name "unconnected-(USBC1-Pad0)") (class "Default")
      (node (ref "USBC1") (pin "0") (pinfunction "0_0") (pintype "input+no_connect"))
    )
    (net (code "82") (name "unconnected-(USBC1-Pad1)") (class "Default")
      (node (ref "USBC1") (pin "1") (pinfunction "1_1") (pintype "input+no_connect"))
    )
    (net (code "83") (name "unconnected-(USBC1-Pad2)") (class "Default")
      (node (ref "USBC1") (pin "2") (pinfunction "2_2") (pintype "input+no_connect"))
    )
    (net (code "84") (name "unconnected-(USBC1-Pad3)") (class "Default")
      (node (ref "USBC1") (pin "3") (pinfunction "3_3") (pintype "input+no_connect"))
    )
    (net (code "85") (name "unconnected-(USBC1-SBU1-PadA8)") (class "Default")
      (node (ref "USBC1") (pin "A8") (pinfunction "SBU1_A8") (pintype "input+no_connect"))
    )
    (net (code "86") (name "unconnected-(USBC1-SBU2-PadB8)") (class "Default")
      (node (ref "USBC1") (pin "B8") (pinfunction "SBU2_B8") (pintype "input+no_connect"))
    )
  )
)
